# Peripherals.net
KiCad netlist of a schematic drawn in Altium Designer
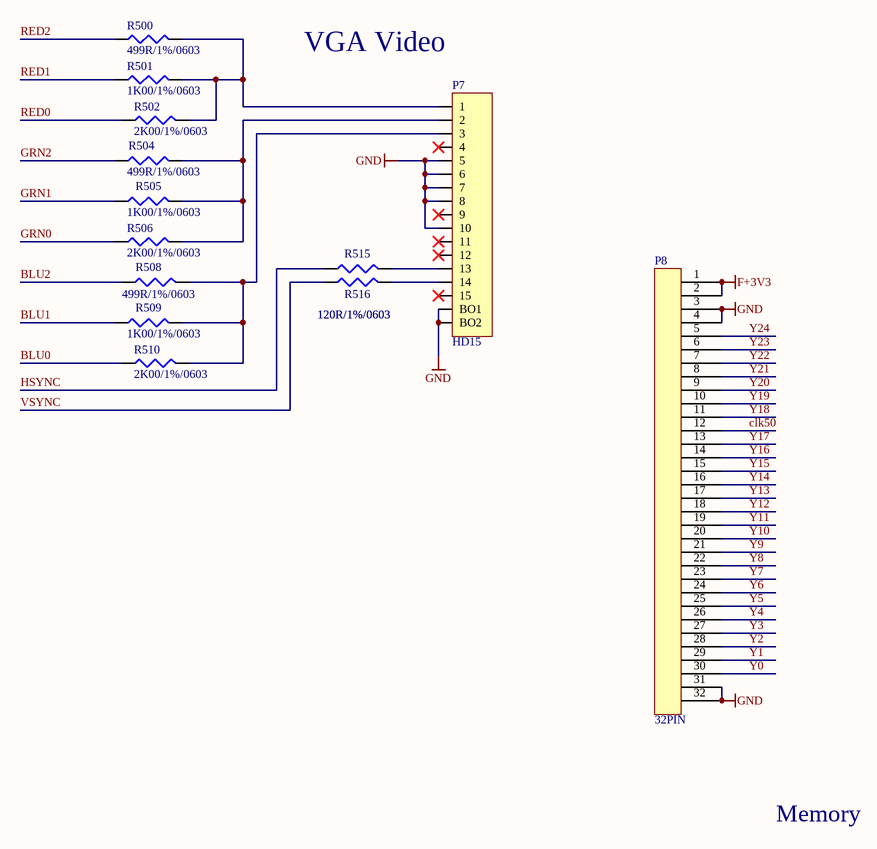
[diagram p0: Peripherals.SchDoc]

(export (version "E")
  (design (tool "Eeschema 10.0.6"))
  (components
    (comp (ref "P7")
      (value "HD15")
      (footprint "DB15FLC")
      (description "CONN DSUB HD RCPT 15POS R/A SLDR")
      (libsource (lib "C64Interface") (part "HD15"))
    )
    (comp (ref "P8") (value "32PIN") (footprint "IDC32") (libsource (lib "Connectors") (part "32PIN")))
    (comp (ref "R500")
      (value "499R/1%/0603")
      (footprint "0603")
      (description "499 Ohms ±1% 0.1W, 1/10W Chip Resistor 0603 (1608 Metric) Moisture Resistant Thick Film")
      (fields (field (name "MFG") "Yeago"))
      (libsource (lib "Resistors") (part "499R/1%/0603"))
    )
    (comp (ref "R501")
      (value "1K00/1%/0603")
      (footprint "0603")
      (description "1 kOhms ±1% 0.1W, 1/10W Chip Resistor 0603 (1608 Metric) Moisture Resistant Thick Film")
      (fields (field (name "MFG") "Yeago"))
      (libsource (lib "Resistors") (part "1K00/1%/0603"))
    )
    (comp (ref "R502")
      (value "2K00/1%/0603")
      (footprint "0603")
      (description "2 kOhms ±1% 0.1W, 1/10W Chip Resistor 0603 (1608 Metric) Moisture Resistant Thick Film")
      (fields (field (name "MFG") "Yeago"))
      (libsource (lib "Resistors") (part "2K00/1%/0603"))
    )
    (comp (ref "R504")
      (value "499R/1%/0603")
      (footprint "0603")
      (description "499 Ohms ±1% 0.1W, 1/10W Chip Resistor 0603 (1608 Metric) Moisture Resistant Thick Film")
      (fields (field (name "MFG") "Yeago"))
      (libsource (lib "Resistors") (part "499R/1%/0603"))
    )
    (comp (ref "R505")
      (value "1K00/1%/0603")
      (footprint "0603")
      (description "1 kOhms ±1% 0.1W, 1/10W Chip Resistor 0603 (1608 Metric) Moisture Resistant Thick Film")
      (fields (field (name "MFG") "Yeago"))
      (libsource (lib "Resistors") (part "1K00/1%/0603"))
    )
    (comp (ref "R506")
      (value "2K00/1%/0603")
      (footprint "0603")
      (description "2 kOhms ±1% 0.1W, 1/10W Chip Resistor 0603 (1608 Metric) Moisture Resistant Thick Film")
      (fields (field (name "MFG") "Yeago"))
      (libsource (lib "Resistors") (part "2K00/1%/0603"))
    )
    (comp (ref "R508")
      (value "499R/1%/0603")
      (footprint "0603")
      (description "499 Ohms ±1% 0.1W, 1/10W Chip Resistor 0603 (1608 Metric) Moisture Resistant Thick Film")
      (fields (field (name "MFG") "Yeago"))
      (libsource (lib "Resistors") (part "499R/1%/0603"))
    )
    (comp (ref "R509")
      (value "1K00/1%/0603")
      (footprint "0603")
      (description "1 kOhms ±1% 0.1W, 1/10W Chip Resistor 0603 (1608 Metric) Moisture Resistant Thick Film")
      (fields (field (name "MFG") "Yeago"))
      (libsource (lib "Resistors") (part "1K00/1%/0603"))
    )
    (comp (ref "R510")
      (value "2K00/1%/0603")
      (footprint "0603")
      (description "2 kOhms ±1% 0.1W, 1/10W Chip Resistor 0603 (1608 Metric) Moisture Resistant Thick Film")
      (fields (field (name "MFG") "Yeago"))
      (libsource (lib "Resistors") (part "2K00/1%/0603"))
    )
    (comp (ref "R515")
      (value "120R/1%/0603")
      (footprint "0603")
      (description "120 Ohms ±1% 0.1W, 1/10W Chip Resistor 0603 (1608 Metric) Moisture Resistant Thick Film")
      (fields (field (name "MFG") "Yaego"))
      (libsource (lib "C64Interface") (part "120R/1%/0603"))
    )
    (comp (ref "R516")
      (value "120R/1%/0603")
      (footprint "0603")
      (description "120 Ohms ±1% 0.1W, 1/10W Chip Resistor 0603 (1608 Metric) Moisture Resistant Thick Film")
      (fields (field (name "MFG") "Yaego"))
      (libsource (lib "C64Interface") (part "120R/1%/0603"))
    )
  )
  (nets
    (net (code "1") (name "/BLU0") (class "Default") (node (ref "R510") (pin "1") (pintype "passive")))
    (net (code "2") (name "/BLU1") (class "Default") (node (ref "R509") (pin "1") (pintype "passive")))
    (net (code "3") (name "/BLU2") (class "Default") (node (ref "R508") (pin "1") (pintype "passive")))
    (net (code "4") (name "/GRN0") (class "Default") (node (ref "R506") (pin "1") (pintype "passive")))
    (net (code "5") (name "/GRN1") (class "Default") (node (ref "R505") (pin "1") (pintype "passive")))
    (net (code "6") (name "/GRN2") (class "Default") (node (ref "R504") (pin "1") (pintype "passive")))
    (net (code "7") (name "/HSYNC") (class "Default") (node (ref "R515") (pin "1") (pintype "passive")))
    (net (code "8") (name "/RED0") (class "Default") (node (ref "R502") (pin "1") (pintype "passive")))
    (net (code "9") (name "/RED1") (class "Default") (node (ref "R501") (pin "1") (pintype "passive")))
    (net (code "10") (name "/RED2") (class "Default") (node (ref "R500") (pin "1") (pintype "passive")))
    (net (code "11") (name "/VSYNC") (class "Default") (node (ref "R516") (pin "1") (pintype "passive")))
    (net (code "12") (name "/Y0") (class "Default") (node (ref "P8") (pin "30") (pintype "passive")))
    (net (code "13") (name "/Y1") (class "Default") (node (ref "P8") (pin "29") (pintype "passive")))
    (net (code "14") (name "/Y2") (class "Default") (node (ref "P8") (pin "28") (pintype "passive")))
    (net (code "15") (name "/Y3") (class "Default") (node (ref "P8") (pin "27") (pintype "passive")))
    (net (code "16") (name "/Y4") (class "Default") (node (ref "P8") (pin "26") (pintype "passive")))
    (net (code "17") (name "/Y5") (class "Default") (node (ref "P8") (pin "25") (pintype "passive")))
    (net (code "18") (name "/Y6") (class "Default") (node (ref "P8") (pin "24") (pintype "passive")))
    (net (code "19") (name "/Y7") (class "Default") (node (ref "P8") (pin "23") (pintype "passive")))
    (net (code "20") (name "/Y8") (class "Default") (node (ref "P8") (pin "22") (pintype "passive")))
    (net (code "21") (name "/Y9") (class "Default") (node (ref "P8") (pin "21") (pintype "passive")))
    (net (code "22") (name "/Y10") (class "Default") (node (ref "P8") (pin "20") (pintype "passive")))
    (net (code "23") (name "/Y11") (class "Default") (node (ref "P8") (pin "19") (pintype "passive")))
    (net (code "24") (name "/Y12") (class "Default") (node (ref "P8") (pin "18") (pintype "passive")))
    (net (code "25") (name "/Y13") (class "Default") (node (ref "P8") (pin "17") (pintype "passive")))
    (net (code "26") (name "/Y14") (class "Default") (node (ref "P8") (pin "16") (pintype "passive")))
    (net (code "27") (name "/Y15") (class "Default") (node (ref "P8") (pin "15") (pintype "passive")))
    (net (code "28") (name "/Y16") (class "Default") (node (ref "P8") (pin "14") (pintype "passive")))
    (net (code "29") (name "/Y17") (class "Default") (node (ref "P8") (pin "13") (pintype "passive")))
    (net (code "30") (name "/Y18") (class "Default") (node (ref "P8") (pin "11") (pintype "passive")))
    (net (code "31") (name "/Y19") (class "Default") (node (ref "P8") (pin "10") (pintype "passive")))
    (net (code "32") (name "/Y20") (class "Default") (node (ref "P8") (pin "9") (pintype "passive")))
    (net (code "33") (name "/Y21") (class "Default") (node (ref "P8") (pin "8") (pintype "passive")))
    (net (code "34") (name "/Y22") (class "Default") (node (ref "P8") (pin "7") (pintype "passive")))
    (net (code "35") (name "/Y23") (class "Default") (node (ref "P8") (pin "6") (pintype "passive")))
    (net (code "36") (name "/Y24") (class "Default") (node (ref "P8") (pin "5") (pintype "passive")))
    (net (code "37") (name "/clk50") (class "Default") (node (ref "P8") (pin "12") (pintype "passive")))
    (net (code "38") (name "F+3V3") (class "Default")
      (node (ref "P8") (pin "1") (pintype "passive"))
      (node (ref "P8") (pin "2") (pintype "passive"))
    )
    (net (code "39") (name "GND") (class "Default")
      (node (ref "P7") (pin "10") (pinfunction "10_10") (pintype "passive"))
      (node (ref "P7") (pin "5") (pinfunction "5_5") (pintype "passive"))
      (node (ref "P7") (pin "6") (pinfunction "6_6") (pintype "passive"))
      (node (ref "P7") (pin "7") (pinfunction "7_7") (pintype "passive"))
      (node (ref "P7") (pin "8") (pinfunction "8_8") (pintype "passive"))
      (node (ref "P7") (pin "BO1") (pinfunction "BO1_BO1") (pintype "passive"))
      (node (ref "P7") (pin "BO2") (pinfunction "BO2_BO2") (pintype "passive"))
      (node (ref "P8") (pin "3") (pintype "passive"))
      (node (ref "P8") (pin "31") (pintype "passive"))
      (node (ref "P8") (pin "32") (pintype "passive"))
      (node (ref "P8") (pin "4") (pintype "passive"))
    )
    (net (code "40") (name "Net-(P7-Pad1)") (class "Default")
      (node (ref "P7") (pin "1") (pinfunction "1_1") (pintype "passive"))
      (node (ref "R500") (pin "2") (pintype "passive"))
      (node (ref "R501") (pin "2") (pintype "passive"))
      (node (ref "R502") (pin "2") (pintype "passive"))
    )
    (net (code "41") (name "Net-(P7-Pad2)") (class "Default")
      (node (ref "P7") (pin "2") (pinfunction "2_2") (pintype "passive"))
      (node (ref "R504") (pin "2") (pintype "passive"))
      (node (ref "R505") (pin "2") (pintype "passive"))
      (node (ref "R506") (pin "2") (pintype "passive"))
    )
    (net (code "42") (name "Net-(P7-Pad3)") (class "Default")
      (node (ref "P7") (pin "3") (pinfunction "3_3") (pintype "passive"))
      (node (ref "R508") (pin "2") (pintype "passive"))
      (node (ref "R509") (pin "2") (pintype "passive"))
      (node (ref "R510") (pin "2") (pintype "passive"))
    )
    (net (code "43") (name "Net-(P7-Pad13)") (class "Default")
      (node (ref "P7") (pin "13") (pinfunction "13_13") (pintype "passive"))
      (node (ref "R515") (pin "2") (pintype "passive"))
    )
    (net (code "44") (name "Net-(P7-Pad14)") (class "Default")
      (node (ref "P7") (pin "14") (pinfunction "14_14") (pintype "passive"))
      (node (ref "R516") (pin "2") (pintype "passive"))
    )
    (net (code "45") (name "unconnected-(P7-Pad4)") (class "Default")
      (node (ref "P7") (pin "4") (pinfunction "4_4") (pintype "passive+no_connect"))
    )
    (net (code "46") (name "unconnected-(P7-Pad9)") (class "Default")
      (node (ref "P7") (pin "9") (pinfunction "9_9") (pintype "passive+no_connect"))
    )
    (net (code "47") (name "unconnected-(P7-Pad11)") (class "Default")
      (node (ref "P7") (pin "11") (pinfunction "11_11") (pintype "passive+no_connect"))
    )
    (net (code "48") (name "unconnected-(P7-Pad12)") (class "Default")
      (node (ref "P7") (pin "12") (pinfunction "12_12") (pintype "passive+no_connect"))
    )
    (net (code "49") (name "unconnected-(P7-Pad15)") (class "Default")
      (node (ref "P7") (pin "15") (pinfunction "15_15") (pintype "passive+no_connect"))
    )
  )
)
